# MSE_Temp_Controller.net
KiCad netlist of a schematic drawn in EAGLE
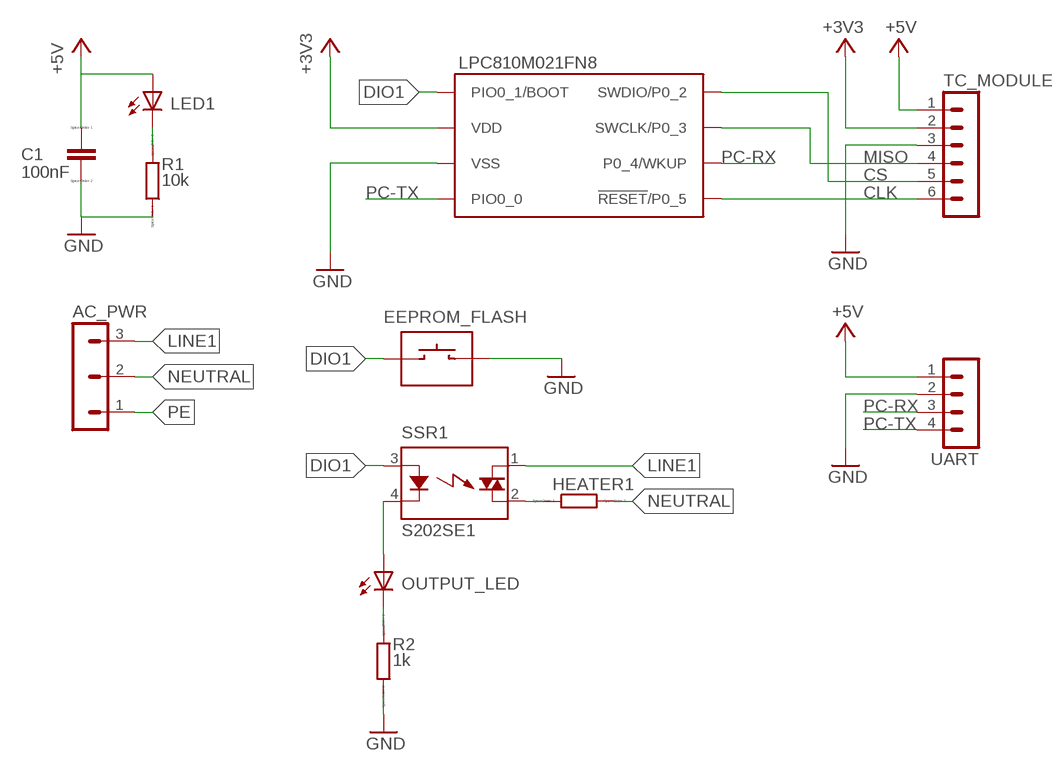
[diagram p0: schematic, sheet 1]

(export (version "E")
  (design (tool "Eeschema 10.0.6"))
  (components
    (comp (ref "AC_PWR")
      (value "MA03-1")
      (footprint "eagle-import:MA03-1")
      (libsource (lib "eagle-import") (part "MA03-1"))
    )
    (comp (ref "C1")
      (value "100nF")
      (footprint "eagle-import:C0603")
      (libsource (lib "eagle-import") (part "CC0603"))
    )
    (comp (ref "D1")
      (value "CLM3C-WKW-CWBYA153")
      (footprint "eagle-import:PLCC2")
      (libsource (lib "eagle-import") (part "CLM3C-WKW-CWBYA153"))
    )
    (comp (ref "D2")
      (value "CLM3C-WKW-CWBYA153")
      (footprint "eagle-import:PLCC2")
      (libsource (lib "eagle-import") (part "CLM3C-WKW-CWBYA153"))
    )
    (comp (ref "HEATER1")
      (value "RR0402")
      (footprint "eagle-import:R0402")
      (libsource (lib "eagle-import") (part "RR0402"))
    )
    (comp (ref "R1")
      (value "10k")
      (footprint "eagle-import:R0402")
      (libsource (lib "eagle-import") (part "RR0402"))
    )
    (comp (ref "R2")
      (value "1k")
      (footprint "eagle-import:R0402")
      (libsource (lib "eagle-import") (part "RR0402"))
    )
    (comp (ref "S1")
      (value "EVQ_Q2_Y01W")
      (footprint "eagle-import:EVQQ2")
      (libsource (lib "eagle-import") (part "EVQ_Q2_Y01W"))
    )
    (comp (ref "SSR1")
      (value "S202SE1")
      (footprint "eagle-import:S2XXEX")
      (libsource (lib "eagle-import") (part "S202SE1"))
    )
    (comp (ref "TC_MODULE")
      (value "MA06-1")
      (footprint "eagle-import:MA06-1")
      (libsource (lib "eagle-import") (part "MA06-1"))
    )
    (comp (ref "U$1")
      (value "LPC810M021FN8")
      (footprint "eagle-import:DIP8")
      (libsource (lib "eagle-import") (part "LPC810M021FN8"))
    )
    (comp (ref "UART")
      (value "MA04-1")
      (footprint "eagle-import:MA04-1")
      (libsource (lib "eagle-import") (part "MA04-1"))
    )
  )
  (nets
    (net (code "1") (name "+3V3") (class "Default")
      (node (ref "TC_MODULE") (pin "2") (pinfunction "2_2") (pintype "passive"))
      (node (ref "U$1") (pin "P$6") (pinfunction "VDD_P$6") (pintype "bidirectional"))
    )
    (net (code "2") (name "+5V") (class "Default")
      (node (ref "C1") (pin "1") (pinfunction "1_1") (pintype "passive"))
      (node (ref "D2") (pin "P$1") (pinfunction "A_P$1") (pintype "passive"))
      (node (ref "TC_MODULE") (pin "1") (pinfunction "1_1") (pintype "passive"))
      (node (ref "UART") (pin "1") (pinfunction "1_1") (pintype "passive"))
    )
    (net (code "3") (name "/CLK") (class "Default")
      (node (ref "TC_MODULE") (pin "6") (pinfunction "6_6") (pintype "passive"))
      (node (ref "U$1") (pin "P$1") (pinfunction "~{RESET}/P0_5_P$1") (pintype "bidirectional"))
    )
    (net (code "4") (name "/CS") (class "Default")
      (node (ref "TC_MODULE") (pin "5") (pinfunction "5_5") (pintype "passive"))
      (node (ref "U$1") (pin "P$4") (pinfunction "SWDIO/P0_2_P$4") (pintype "bidirectional"))
    )
    (net (code "5") (name "/MISO") (class "Default")
      (node (ref "TC_MODULE") (pin "4") (pinfunction "4_4") (pintype "passive"))
      (node (ref "U$1") (pin "P$3") (pinfunction "SWCLK/P0_3_P$3") (pintype "bidirectional"))
    )
    (net (code "6") (name "/PC-RX") (class "Default")
      (node (ref "U$1") (pin "P$2") (pinfunction "P0_4/WKUP_P$2") (pintype "bidirectional"))
      (node (ref "UART") (pin "3") (pinfunction "3_3") (pintype "passive"))
    )
    (net (code "7") (name "/PC-TX") (class "Default")
      (node (ref "U$1") (pin "P$8") (pinfunction "PIO0_0_P$8") (pintype "bidirectional"))
      (node (ref "UART") (pin "4") (pinfunction "4_4") (pintype "passive"))
    )
    (net (code "8") (name "DIO1") (class "Default")
      (node (ref "S1") (pin "A1") (pinfunction "A_A1") (pintype "bidirectional"))
      (node (ref "S1") (pin "A2") (pinfunction "A_A2") (pintype "bidirectional"))
      (node (ref "SSR1") (pin "3") (pinfunction "A_3") (pintype "passive"))
      (node (ref "U$1") (pin "P$5") (pinfunction "PIO0_1/BOOT_P$5") (pintype "bidirectional"))
    )
    (net (code "9") (name "GND") (class "Default")
      (node (ref "C1") (pin "2") (pinfunction "2_2") (pintype "passive"))
      (node (ref "R1") (pin "1") (pinfunction "1_1") (pintype "passive"))
      (node (ref "R2") (pin "2") (pinfunction "2_2") (pintype "passive"))
      (node (ref "S1") (pin "B1") (pinfunction "B_B1") (pintype "bidirectional"))
      (node (ref "S1") (pin "B2") (pinfunction "B_B2") (pintype "bidirectional"))
      (node (ref "TC_MODULE") (pin "3") (pinfunction "3_3") (pintype "passive"))
      (node (ref "U$1") (pin "P$7") (pinfunction "VSS_P$7") (pintype "bidirectional"))
      (node (ref "UART") (pin "2") (pinfunction "2_2") (pintype "passive"))
    )
    (net (code "10") (name "LINE1") (class "Default")
      (node (ref "AC_PWR") (pin "3") (pinfunction "3_3") (pintype "passive"))
      (node (ref "SSR1") (pin "1") (pinfunction "DS1_1") (pintype "passive"))
    )
    (net (code "11") (name "NEUTRAL") (class "Default")
      (node (ref "AC_PWR") (pin "2") (pinfunction "2_2") (pintype "passive"))
      (node (ref "HEATER1") (pin "2") (pinfunction "2_2") (pintype "passive"))
    )
    (net (code "12") (name "Net-(D1-A)") (class "Default")
      (node (ref "D1") (pin "P$1") (pinfunction "A_P$1") (pintype "passive"))
      (node (ref "SSR1") (pin "4") (pinfunction "K_4") (pintype "passive"))
    )
    (net (code "13") (name "Net-(D1-C)") (class "Default")
      (node (ref "D1") (pin "P$2") (pinfunction "C_P$2") (pintype "passive"))
      (node (ref "R2") (pin "1") (pinfunction "1_1") (pintype "passive"))
    )
    (net (code "14") (name "Net-(D2-C)") (class "Default")
      (node (ref "D2") (pin "P$2") (pinfunction "C_P$2") (pintype "passive"))
      (node (ref "R1") (pin "2") (pinfunction "2_2") (pintype "passive"))
    )
    (net (code "15") (name "Net-(SSR1-DS2)") (class "Default")
      (node (ref "HEATER1") (pin "1") (pinfunction "1_1") (pintype "passive"))
      (node (ref "SSR1") (pin "2") (pinfunction "DS2_2") (pintype "passive"))
    )
    (net (code "16") (name "PE") (class "Default")
      (node (ref "AC_PWR") (pin "1") (pinfunction "1_1") (pintype "passive"))
    )
  )
)
